# 011_TempSensors.net
KiCad netlist of a schematic drawn in Altium Designer
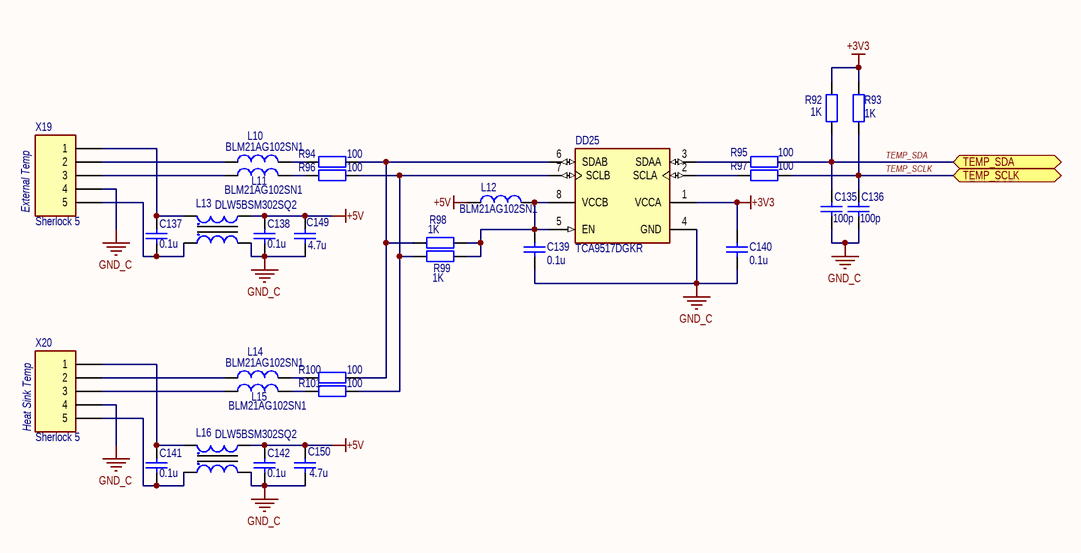
[diagram p0: 011_TempSensors.SchDoc]

(export (version "E")
  (design (tool "Eeschema 10.0.6"))
  (components
    (comp (ref "C135")
      (value "100p")
      (footprint "mainLib:SMD_C_0603")
      (description "SMD C 0603 MURATA 100V 5% NP0")
      (fields (field (name "PARTNUMBER") "GRM1885C2A101JA01") (field (name "MANUFACTURER") "MURATA"))
      (libsource (lib "mainRCLib") (part "C0603 100p 100V 5%"))
    )
    (comp (ref "C136")
      (value "100p")
      (footprint "mainLib:SMD_C_0603")
      (description "SMD C 0603 MURATA 100V 5% NP0")
      (fields (field (name "PARTNUMBER") "GRM1885C2A101JA01") (field (name "MANUFACTURER") "MURATA"))
      (libsource (lib "mainRCLib") (part "C0603 100p 100V 5%"))
    )
    (comp (ref "C137")
      (value "0.1u")
      (footprint "mainLib:SMD_C_0603")
      (description "SMD C 0603 MURATA 50V 10% X7R")
      (fields (field (name "PARTNUMBER") "GRM188R71H104K") (field (name "MANUFACTURER") "MURATA"))
      (libsource (lib "mainRCLib") (part "C0603 0.1u 50V 10%"))
    )
    (comp (ref "C138")
      (value "0.1u")
      (footprint "mainLib:SMD_C_0603")
      (description "SMD C 0603 MURATA 50V 10% X7R")
      (fields (field (name "PARTNUMBER") "GRM188R71H104K") (field (name "MANUFACTURER") "MURATA"))
      (libsource (lib "mainRCLib") (part "C0603 0.1u 50V 10%"))
    )
    (comp (ref "C139")
      (value "0.1u")
      (footprint "mainLib:SMD_C_0603")
      (description "SMD C 0603 MURATA 50V 10% X7R")
      (fields (field (name "PARTNUMBER") "GRM188R71H104K") (field (name "MANUFACTURER") "MURATA"))
      (libsource (lib "mainRCLib") (part "C0603 0.1u 50V 10%"))
    )
    (comp (ref "C140")
      (value "0.1u")
      (footprint "mainLib:SMD_C_0603")
      (description "SMD C 0603 MURATA 50V 10% X7R")
      (fields (field (name "PARTNUMBER") "GRM188R71H104K") (field (name "MANUFACTURER") "MURATA"))
      (libsource (lib "mainRCLib") (part "C0603 0.1u 50V 10%"))
    )
    (comp (ref "C141")
      (value "0.1u")
      (footprint "mainLib:SMD_C_0603")
      (description "SMD C 0603 MURATA 50V 10% X7R")
      (fields (field (name "PARTNUMBER") "GRM188R71H104K") (field (name "MANUFACTURER") "MURATA"))
      (libsource (lib "mainRCLib") (part "C0603 0.1u 50V 10%"))
    )
    (comp (ref "C142")
      (value "0.1u")
      (footprint "mainLib:SMD_C_0603")
      (description "SMD C 0603 MURATA 50V 10% X7R")
      (fields (field (name "PARTNUMBER") "GRM188R71H104K") (field (name "MANUFACTURER") "MURATA"))
      (libsource (lib "mainRCLib") (part "C0603 0.1u 50V 10%"))
    )
    (comp (ref "C149")
      (value "4.7u")
      (footprint "mainLib:SMD_C_0805")
      (description "SMD C 0805 MURATA 50V 5% NP0")
      (fields (field (name "PARTNUMBER") "GRM21BR61E475M") (field (name "MANUFACTURER") "MURATA"))
      (libsource (lib "mainRCLib") (part "C0805 4.7u 25V 20%  X5R"))
    )
    (comp (ref "C150")
      (value "4.7u")
      (footprint "mainLib:SMD_C_0805")
      (description "SMD C 0805 MURATA 50V 5% NP0")
      (fields (field (name "PARTNUMBER") "GRM21BR61E475M") (field (name "MANUFACTURER") "MURATA"))
      (libsource (lib "mainRCLib") (part "C0805 4.7u 25V 20%  X5R"))
    )
    (comp (ref "DD25")
      (value "TCA9517DGKR")
      (footprint "mainLib:DGK8_M")
      (description "Level-Shifting I 2C Bus Repeater")
      (fields (field (name "MANUFACTURER") "Texas Instruments"))
      (libsource (lib "mainLib") (part "TCA9517DGKR"))
    )
    (comp (ref "L10")
      (value "BLM21AG102SN1")
      (footprint "mainLib:SMD_L_L2_W1.25")
      (description "1000R 0.6A (100MHz)")
      (fields (field (name "MANUFACTURER") "TDK"))
      (libsource (lib "mainLib") (part "BLM21AG102SN1"))
    )
    (comp (ref "L11")
      (value "BLM21AG102SN1")
      (footprint "mainLib:SMD_L_L2_W1.25")
      (description "1000R 0.6A (100MHz)")
      (fields (field (name "MANUFACTURER") "TDK"))
      (libsource (lib "mainLib") (part "BLM21AG102SN1"))
    )
    (comp (ref "L12")
      (value "BLM21AG102SN1")
      (footprint "mainLib:SMD_L_L2_W1.25")
      (description "1000R 0.6A (100MHz)")
      (fields (field (name "MANUFACTURER") "TDK"))
      (libsource (lib "mainLib") (part "BLM21AG102SN1"))
    )
    (comp (ref "L13")
      (value "DLW5BSM302SQ2")
      (footprint "mainLib:DLW5BS(AH)")
      (description "SMD Common Mode Choke Coil 0.5A Z = 3000 Ohm / 100 MHz")
      (fields (field (name "MANUFACTURER") "MURATA"))
      (libsource (lib "mainLib") (part "DLW5BSM302SQ2"))
    )
    (comp (ref "L14")
      (value "BLM21AG102SN1")
      (footprint "mainLib:SMD_L_L2_W1.25")
      (description "1000R 0.6A (100MHz)")
      (fields (field (name "MANUFACTURER") "TDK"))
      (libsource (lib "mainLib") (part "BLM21AG102SN1"))
    )
    (comp (ref "L15")
      (value "BLM21AG102SN1")
      (footprint "mainLib:SMD_L_L2_W1.25")
      (description "1000R 0.6A (100MHz)")
      (fields (field (name "MANUFACTURER") "TDK"))
      (libsource (lib "mainLib") (part "BLM21AG102SN1"))
    )
    (comp (ref "L16")
      (value "DLW5BSM302SQ2")
      (footprint "mainLib:DLW5BS(AH)")
      (description "SMD Common Mode Choke Coil 0.5A Z = 3000 Ohm / 100 MHz")
      (fields (field (name "MANUFACTURER") "MURATA"))
      (libsource (lib "mainLib") (part "DLW5BSM302SQ2"))
    )
    (comp (ref "R92")
      (value "1K")
      (footprint "mainLib:SMD_R_0603")
      (description "SMD R 0603 VISHAY 0.1W 75V 1% 100ppm")
      (fields (field (name "PARTNUMBER") "CRCW06031K00FK") (field (name "MANUFACTURER") "VISHAY"))
      (libsource (lib "") (part "R0603 1K 1%_1"))
    )
    (comp (ref "R93")
      (value "1K")
      (footprint "mainLib:SMD_R_0603")
      (description "SMD R 0603 VISHAY 0.1W 75V 1% 100ppm")
      (fields (field (name "PARTNUMBER") "CRCW06031K00FK") (field (name "MANUFACTURER") "VISHAY"))
      (libsource (lib "") (part "R0603 1K 1%_1"))
    )
    (comp (ref "R94")
      (value "100")
      (footprint "SMD_R_0603")
      (description "SMD R 0603 VISHAY 0.1W 75V 1% 100ppm")
      (fields (field (name "PARTNUMBER") "CRCW0603100RFK") (field (name "MANUFACTURER") "VISHAY"))
      (libsource (lib "mainRCLib") (part "R0603 100 1%"))
    )
    (comp (ref "R95")
      (value "100")
      (footprint "SMD_R_0603")
      (description "SMD R 0603 VISHAY 0.1W 75V 1% 100ppm")
      (fields (field (name "PARTNUMBER") "CRCW0603100RFK") (field (name "MANUFACTURER") "VISHAY"))
      (libsource (lib "mainRCLib") (part "R0603 100 1%"))
    )
    (comp (ref "R96")
      (value "100")
      (footprint "SMD_R_0603")
      (description "SMD R 0603 VISHAY 0.1W 75V 1% 100ppm")
      (fields (field (name "PARTNUMBER") "CRCW0603100RFK") (field (name "MANUFACTURER") "VISHAY"))
      (libsource (lib "mainRCLib") (part "R0603 100 1%"))
    )
    (comp (ref "R97")
      (value "100")
      (footprint "SMD_R_0603")
      (description "SMD R 0603 VISHAY 0.1W 75V 1% 100ppm")
      (fields (field (name "PARTNUMBER") "CRCW0603100RFK") (field (name "MANUFACTURER") "VISHAY"))
      (libsource (lib "mainRCLib") (part "R0603 100 1%"))
    )
    (comp (ref "R98")
      (value "1K")
      (footprint "mainLib:SMD_R_0603")
      (description "SMD R 0603 VISHAY 0.1W 75V 1% 100ppm")
      (fields (field (name "PARTNUMBER") "CRCW06031K00FK") (field (name "MANUFACTURER") "VISHAY"))
      (libsource (lib "mainRCLib") (part "R0603 1K 1%"))
    )
    (comp (ref "R99")
      (value "1K")
      (footprint "mainLib:SMD_R_0603")
      (description "SMD R 0603 VISHAY 0.1W 75V 1% 100ppm")
      (fields (field (name "PARTNUMBER") "CRCW06031K00FK") (field (name "MANUFACTURER") "VISHAY"))
      (libsource (lib "mainRCLib") (part "R0603 1K 1%"))
    )
    (comp (ref "R100")
      (value "100")
      (footprint "SMD_R_0603")
      (description "SMD R 0603 VISHAY 0.1W 75V 1% 100ppm")
      (fields (field (name "PARTNUMBER") "CRCW0603100RFK") (field (name "MANUFACTURER") "VISHAY"))
      (libsource (lib "mainRCLib") (part "R0603 100 1%"))
    )
    (comp (ref "R101")
      (value "100")
      (footprint "SMD_R_0603")
      (description "SMD R 0603 VISHAY 0.1W 75V 1% 100ppm")
      (fields (field (name "PARTNUMBER") "CRCW0603100RFK") (field (name "MANUFACTURER") "VISHAY"))
      (libsource (lib "mainRCLib") (part "R0603 100 1%"))
    )
    (comp (ref "X19")
      (value "Sherlock 5")
      (footprint "mainLib:35362-0550")
      (description "Sherlock 5 Top, 2A 125V 2mm")
      (fields (field (name "PARTNUMBER") "35362-0550") (field (name "MANUFACTURER") "MOLEX"))
      (libsource (lib "mainLib") (part "35362-0550"))
    )
    (comp (ref "X20")
      (value "Sherlock 5")
      (footprint "mainLib:35362-0550")
      (description "Sherlock 5 Top, 2A 125V 2mm")
      (fields (field (name "PARTNUMBER") "35362-0550") (field (name "MANUFACTURER") "MOLEX"))
      (libsource (lib "mainLib") (part "35362-0550"))
    )
  )
  (nets
    (net (code "1") (name "+3V3") (class "Default")
      (node (ref "C140") (pin "2") (pinfunction "2_2") (pintype "passive"))
      (node (ref "DD25") (pin "1") (pinfunction "VCCA_1") (pintype "power_in"))
      (node (ref "R92") (pin "2") (pinfunction "2_2") (pintype "passive"))
      (node (ref "R93") (pin "2") (pinfunction "2_2") (pintype "passive"))
    )
    (net (code "2") (name "+5V") (class "Default")
      (node (ref "C138") (pin "2") (pinfunction "2_2") (pintype "passive"))
      (node (ref "C142") (pin "2") (pinfunction "2_2") (pintype "passive"))
      (node (ref "C149") (pin "2") (pinfunction "2_2") (pintype "passive"))
      (node (ref "C150") (pin "2") (pinfunction "2_2") (pintype "passive"))
      (node (ref "L12") (pin "1") (pinfunction "1_1") (pintype "passive"))
      (node (ref "L13") (pin "3") (pinfunction "3_3") (pintype "passive"))
      (node (ref "L16") (pin "3") (pinfunction "3_3") (pintype "passive"))
    )
    (net (code "3") (name "/TEMP_SCLK") (class "Default")
      (node (ref "C136") (pin "2") (pinfunction "2_2") (pintype "passive"))
      (node (ref "R93") (pin "1") (pinfunction "1_1") (pintype "passive"))
      (node (ref "R97") (pin "2") (pinfunction "2_2") (pintype "passive"))
    )
    (net (code "4") (name "/TEMP_SDA") (class "Default")
      (node (ref "C135") (pin "2") (pinfunction "2_2") (pintype "passive"))
      (node (ref "R92") (pin "1") (pinfunction "1_1") (pintype "passive"))
      (node (ref "R95") (pin "2") (pinfunction "2_2") (pintype "passive"))
    )
    (net (code "5") (name "GND_C") (class "Default")
      (node (ref "C135") (pin "1") (pinfunction "1_1") (pintype "passive"))
      (node (ref "C136") (pin "1") (pinfunction "1_1") (pintype "passive"))
      (node (ref "C138") (pin "1") (pinfunction "1_1") (pintype "passive"))
      (node (ref "C139") (pin "1") (pinfunction "1_1") (pintype "passive"))
      (node (ref "C140") (pin "1") (pinfunction "1_1") (pintype "passive"))
      (node (ref "C142") (pin "1") (pinfunction "1_1") (pintype "passive"))
      (node (ref "C149") (pin "1") (pinfunction "1_1") (pintype "passive"))
      (node (ref "C150") (pin "1") (pinfunction "1_1") (pintype "passive"))
      (node (ref "DD25") (pin "4") (pinfunction "GND_4") (pintype "power_in"))
      (node (ref "L13") (pin "2") (pinfunction "2_2") (pintype "passive"))
      (node (ref "L16") (pin "2") (pinfunction "2_2") (pintype "passive"))
      (node (ref "X19") (pin "4") (pinfunction "4_4") (pintype "passive"))
      (node (ref "X20") (pin "4") (pinfunction "4_4") (pintype "passive"))
    )
    (net (code "6") (name "Net-(C137-Pad1)") (class "Default")
      (node (ref "C137") (pin "1") (pinfunction "1_1") (pintype "passive"))
      (node (ref "L13") (pin "1") (pinfunction "1_1") (pintype "passive"))
      (node (ref "X19") (pin "5") (pinfunction "5_5") (pintype "passive"))
    )
    (net (code "7") (name "Net-(C137-Pad2)") (class "Default")
      (node (ref "C137") (pin "2") (pinfunction "2_2") (pintype "passive"))
      (node (ref "L13") (pin "4") (pinfunction "4_4") (pintype "passive"))
      (node (ref "X19") (pin "1") (pinfunction "1_1") (pintype "passive"))
    )
    (net (code "8") (name "Net-(C141-Pad1)") (class "Default")
      (node (ref "C141") (pin "1") (pinfunction "1_1") (pintype "passive"))
      (node (ref "L16") (pin "1") (pinfunction "1_1") (pintype "passive"))
      (node (ref "X20") (pin "5") (pinfunction "5_5") (pintype "passive"))
    )
    (net (code "9") (name "Net-(C141-Pad2)") (class "Default")
      (node (ref "C141") (pin "2") (pinfunction "2_2") (pintype "passive"))
      (node (ref "L16") (pin "4") (pinfunction "4_4") (pintype "passive"))
      (node (ref "X20") (pin "1") (pinfunction "1_1") (pintype "passive"))
    )
    (net (code "10") (name "Net-(DD25-EN)") (class "Default")
      (node (ref "C139") (pin "2") (pinfunction "2_2") (pintype "passive"))
      (node (ref "DD25") (pin "5") (pinfunction "EN_5") (pintype "input"))
      (node (ref "DD25") (pin "8") (pinfunction "VCCB_8") (pintype "power_in"))
      (node (ref "L12") (pin "2") (pinfunction "2_2") (pintype "passive"))
      (node (ref "R98") (pin "1") (pinfunction "1_1") (pintype "passive"))
      (node (ref "R99") (pin "1") (pinfunction "1_1") (pintype "passive"))
    )
    (net (code "11") (name "Net-(DD25-SCLA)") (class "Default")
      (node (ref "DD25") (pin "2") (pinfunction "SCLA_2") (pintype "bidirectional"))
      (node (ref "R97") (pin "1") (pinfunction "1_1") (pintype "passive"))
    )
    (net (code "12") (name "Net-(DD25-SCLB)") (class "Default")
      (node (ref "DD25") (pin "7") (pinfunction "SCLB_7") (pintype "bidirectional"))
      (node (ref "R101") (pin "2") (pinfunction "2_2") (pintype "passive"))
      (node (ref "R96") (pin "2") (pinfunction "2_2") (pintype "passive"))
      (node (ref "R99") (pin "2") (pinfunction "2_2") (pintype "passive"))
    )
    (net (code "13") (name "Net-(DD25-SDAA)") (class "Default")
      (node (ref "DD25") (pin "3") (pinfunction "SDAA_3") (pintype "bidirectional"))
      (node (ref "R95") (pin "1") (pinfunction "1_1") (pintype "passive"))
    )
    (net (code "14") (name "Net-(DD25-SDAB)") (class "Default")
      (node (ref "DD25") (pin "6") (pinfunction "SDAB_6") (pintype "bidirectional"))
      (node (ref "R100") (pin "2") (pinfunction "2_2") (pintype "passive"))
      (node (ref "R94") (pin "2") (pinfunction "2_2") (pintype "passive"))
      (node (ref "R98") (pin "2") (pinfunction "2_2") (pintype "passive"))
    )
    (net (code "15") (name "Net-(L10-Pad1)") (class "Default")
      (node (ref "L10") (pin "1") (pinfunction "1_1") (pintype "passive"))
      (node (ref "X19") (pin "2") (pinfunction "2_2") (pintype "passive"))
    )
    (net (code "16") (name "Net-(L10-Pad2)") (class "Default")
      (node (ref "L10") (pin "2") (pinfunction "2_2") (pintype "passive"))
      (node (ref "R94") (pin "1") (pinfunction "1_1") (pintype "passive"))
    )
    (net (code "17") (name "Net-(L11-Pad1)") (class "Default")
      (node (ref "L11") (pin "1") (pinfunction "1_1") (pintype "passive"))
      (node (ref "X19") (pin "3") (pinfunction "3_3") (pintype "passive"))
    )
    (net (code "18") (name "Net-(L11-Pad2)") (class "Default")
      (node (ref "L11") (pin "2") (pinfunction "2_2") (pintype "passive"))
      (node (ref "R96") (pin "1") (pinfunction "1_1") (pintype "passive"))
    )
    (net (code "19") (name "Net-(L14-Pad1)") (class "Default")
      (node (ref "L14") (pin "1") (pinfunction "1_1") (pintype "passive"))
      (node (ref "X20") (pin "2") (pinfunction "2_2") (pintype "passive"))
    )
    (net (code "20") (name "Net-(L14-Pad2)") (class "Default")
      (node (ref "L14") (pin "2") (pinfunction "2_2") (pintype "passive"))
      (node (ref "R100") (pin "1") (pinfunction "1_1") (pintype "passive"))
    )
    (net (code "21") (name "Net-(L15-Pad1)") (class "Default")
      (node (ref "L15") (pin "1") (pinfunction "1_1") (pintype "passive"))
      (node (ref "X20") (pin "3") (pinfunction "3_3") (pintype "passive"))
    )
    (net (code "22") (name "Net-(L15-Pad2)") (class "Default")
      (node (ref "L15") (pin "2") (pinfunction "2_2") (pintype "passive"))
      (node (ref "R101") (pin "1") (pinfunction "1_1") (pintype "passive"))
    )
  )
)
